# Digitizer.net
KiCad netlist of a schematic drawn in Altium Designer
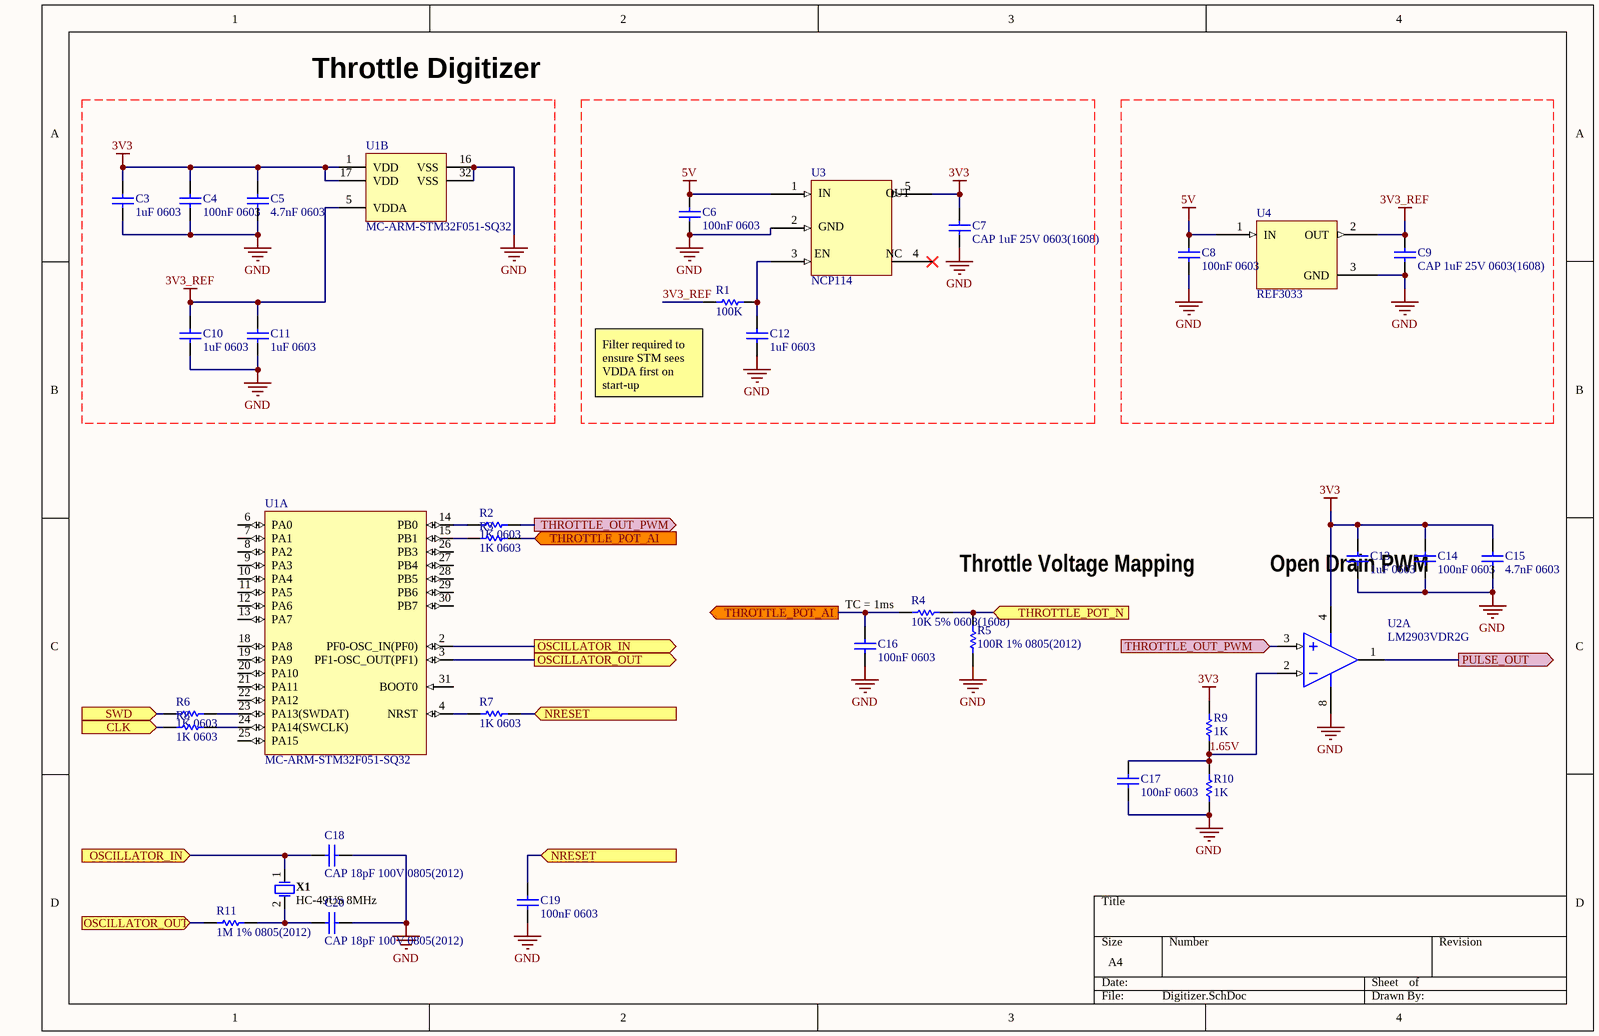
[diagram p0: Digitizer.SchDoc]

(export (version "E")
  (design (tool "Eeschema 10.0.6"))
  (components
    (comp (ref "C3")
      (value "1uF 0603")
      (footprint "CAPC0603(1608)100_M")
      (description "CAP 1uF 25V -20% to +80% 0603 (1608 Metric) Thickness 1mm SMD")
      (fields (field (name "TOLERANCE") "-20% to +80%"))
      (libsource (lib "Altium Content Vault") (part "CMP-1035-02742-1"))
    )
    (comp (ref "C4")
      (value "100nF 0603")
      (footprint "CAPC0603(1608)100_M")
      (description "CAP 1uF 25V -20% to +80% 0603 (1608 Metric) Thickness 1mm SMD")
      (fields (field (name "TOLERANCE") "-20% to +80%"))
      (libsource (lib "Altium Content Vault") (part "CMP-1035-02742-1"))
    )
    (comp (ref "C5")
      (value "4.7nF 0603")
      (footprint "CAPC0603(1608)100_M")
      (description "CAP 1uF 25V -20% to +80% 0603 (1608 Metric) Thickness 1mm SMD")
      (fields (field (name "TOLERANCE") "-20% to +80%"))
      (libsource (lib "Altium Content Vault") (part "CMP-1035-02742-1"))
    )
    (comp (ref "C6")
      (value "100nF 0603")
      (footprint "CAPC0603(1608)100_M")
      (description "CAP 1uF 25V -20% to +80% 0603 (1608 Metric) Thickness 1mm SMD")
      (fields (field (name "TOLERANCE") "-20% to +80%"))
      (libsource (lib "Altium Content Vault") (part "CMP-1035-02742-1"))
    )
    (comp (ref "C7")
      (value "CAP 1uF 25V 0603(1608)")
      (footprint "CAPC0603(1608)100_M")
      (description "CAP 1uF 25V -20% to +80% 0603 (1608 Metric) Thickness 1mm SMD")
      (fields (field (name "TOLERANCE") "-20% to +80%"))
      (libsource (lib "Altium Content Vault") (part "CAP"))
    )
    (comp (ref "C8")
      (value "100nF 0603")
      (footprint "CAPC0603(1608)100_M")
      (description "CAP 1uF 25V -20% to +80% 0603 (1608 Metric) Thickness 1mm SMD")
      (fields (field (name "TOLERANCE") "-20% to +80%"))
      (libsource (lib "Altium Content Vault") (part "CMP-1035-02742-1"))
    )
    (comp (ref "C9")
      (value "CAP 1uF 25V 0603(1608)")
      (footprint "CAPC0603(1608)100_M")
      (description "CAP 1uF 25V -20% to +80% 0603 (1608 Metric) Thickness 1mm SMD")
      (fields (field (name "TOLERANCE") "-20% to +80%"))
      (libsource (lib "Altium Content Vault") (part "CAP"))
    )
    (comp (ref "C10")
      (value "1uF 0603")
      (footprint "CAPC0603(1608)100_M")
      (description "CAP 1uF 25V -20% to +80% 0603 (1608 Metric) Thickness 1mm SMD")
      (fields (field (name "TOLERANCE") "-20% to +80%"))
      (libsource (lib "Altium Content Vault") (part "CMP-1035-02742-1"))
    )
    (comp (ref "C11")
      (value "1uF 0603")
      (footprint "CAPC0603(1608)100_M")
      (description "CAP 1uF 25V -20% to +80% 0603 (1608 Metric) Thickness 1mm SMD")
      (fields (field (name "TOLERANCE") "-20% to +80%"))
      (libsource (lib "Altium Content Vault") (part "CMP-1035-02742-1"))
    )
    (comp (ref "C12")
      (value "1uF 0603")
      (footprint "CAPC0603(1608)100_M")
      (description "CAP 1uF 25V -20% to +80% 0603 (1608 Metric) Thickness 1mm SMD")
      (fields (field (name "TOLERANCE") "-20% to +80%"))
      (libsource (lib "Altium Content Vault") (part "CMP-1035-02742-1"))
    )
    (comp (ref "C13")
      (value "1uF 0603")
      (footprint "CAPC0603(1608)100_M")
      (description "CAP 1uF 25V -20% to +80% 0603 (1608 Metric) Thickness 1mm SMD")
      (fields (field (name "TOLERANCE") "-20% to +80%"))
      (libsource (lib "Altium Content Vault") (part "CMP-1035-02742-1"))
    )
    (comp (ref "C14")
      (value "100nF 0603")
      (footprint "CAPC0603(1608)100_M")
      (description "CAP 1uF 25V -20% to +80% 0603 (1608 Metric) Thickness 1mm SMD")
      (fields (field (name "TOLERANCE") "-20% to +80%"))
      (libsource (lib "Altium Content Vault") (part "CMP-1035-02742-1"))
    )
    (comp (ref "C15")
      (value "4.7nF 0603")
      (footprint "CAPC0603(1608)100_M")
      (description "CAP 1uF 25V -20% to +80% 0603 (1608 Metric) Thickness 1mm SMD")
      (fields (field (name "TOLERANCE") "-20% to +80%"))
      (libsource (lib "Altium Content Vault") (part "CMP-1035-02742-1"))
    )
    (comp (ref "C16")
      (value "100nF 0603")
      (footprint "CAPC0603(1608)100_M")
      (description "CAP 1uF 25V -20% to +80% 0603 (1608 Metric) Thickness 1mm SMD")
      (fields (field (name "TOLERANCE") "-20% to +80%"))
      (libsource (lib "Altium Content Vault") (part "CMP-1035-02742-1"))
    )
    (comp (ref "C17")
      (value "100nF 0603")
      (footprint "CAPC0603(1608)100_M")
      (description "CAP 1uF 25V -20% to +80% 0603 (1608 Metric) Thickness 1mm SMD")
      (fields (field (name "TOLERANCE") "-20% to +80%"))
      (libsource (lib "Altium Content Vault") (part "CMP-1035-02742-1"))
    )
    (comp (ref "C18")
      (value "CAP 18pF 100V 0805(2012)")
      (footprint "CAPC0805(2012)145_L")
      (description "CAP 18pF 100V ±10% 0805 (2012 Metric) Thickness 1.45mm SMD")
      (fields (field (name "TOLERANCE") "Â±10%"))
      (libsource (lib "Altium Content Vault") (part "CMP-1036-01160-1"))
    )
    (comp (ref "C19")
      (value "100nF 0603")
      (footprint "CAPC0603(1608)100_M")
      (description "CAP 1uF 25V -20% to +80% 0603 (1608 Metric) Thickness 1mm SMD")
      (fields (field (name "TOLERANCE") "-20% to +80%"))
      (libsource (lib "Altium Content Vault") (part "CMP-1035-02742-1"))
    )
    (comp (ref "C20")
      (value "CAP 18pF 100V 0805(2012)")
      (footprint "CAPC0805(2012)145_L")
      (description "CAP 18pF 100V ±10% 0805 (2012 Metric) Thickness 1.45mm SMD")
      (fields (field (name "TOLERANCE") "Â±10%"))
      (libsource (lib "Altium Content Vault") (part "CMP-1036-01160-1"))
    )
    (comp (ref "R1")
      (value "100K")
      (footprint "RESC0603(1608)_N")
      (description "2K 0.1W 1% 0603 (1608 Metric)  SMD")
      (fields (field (name "POWER") "0.1 W") (field (name "TOLERANCE") "1 %"))
      (libsource (lib "Altium Content Vault") (part "CMP-1012-00542-1"))
    )
    (comp (ref "R2")
      (value "1K 0603")
      (footprint "RESC0603(1608)_N")
      (description "2K 0.1W 1% 0603 (1608 Metric)  SMD")
      (fields (field (name "POWER") "0.1 W") (field (name "TOLERANCE") "1 %"))
      (libsource (lib "Altium Content Vault") (part "CMP-1012-00542-1"))
    )
    (comp (ref "R3")
      (value "1K 0603")
      (footprint "RESC0603(1608)_N")
      (description "2K 0.1W 1% 0603 (1608 Metric)  SMD")
      (fields (field (name "POWER") "0.1 W") (field (name "TOLERANCE") "1 %"))
      (libsource (lib "Altium Content Vault") (part "CMP-1012-00542-1"))
    )
    (comp (ref "R4")
      (value "10K 5% 0603(1608)")
      (footprint "RESC0603(1608)_M")
      (description "10K 0.1W 5% 0603 (1608 Metric)  SMD")
      (fields (field (name "TOLERANCE") "5 %") (field (name "POWER") "0.1 W"))
      (libsource (lib "Altium Content Vault") (part "CMP-1012-00098-1"))
    )
    (comp (ref "R5")
      (value "100R 1% 0805(2012)")
      (footprint "RESC0805(2012)_M")
      (description "100R 0.125W 1% 0805 (2012 Metric)  SMD")
      (fields (field (name "POWER") "0.125 W") (field (name "TOLERANCE") "1 %"))
      (libsource (lib "Altium Content Vault") (part "RES"))
    )
    (comp (ref "R6")
      (value "1K 0603")
      (footprint "RESC0603(1608)_N")
      (description "2K 0.1W 1% 0603 (1608 Metric)  SMD")
      (fields (field (name "POWER") "0.1 W") (field (name "TOLERANCE") "1 %"))
      (libsource (lib "Altium Content Vault") (part "CMP-1012-00542-1"))
    )
    (comp (ref "R7")
      (value "1K 0603")
      (footprint "RESC0603(1608)_N")
      (description "2K 0.1W 1% 0603 (1608 Metric)  SMD")
      (fields (field (name "POWER") "0.1 W") (field (name "TOLERANCE") "1 %"))
      (libsource (lib "Altium Content Vault") (part "CMP-1012-00542-1"))
    )
    (comp (ref "R8")
      (value "1K 0603")
      (footprint "RESC0603(1608)_N")
      (description "2K 0.1W 1% 0603 (1608 Metric)  SMD")
      (fields (field (name "POWER") "0.1 W") (field (name "TOLERANCE") "1 %"))
      (libsource (lib "Altium Content Vault") (part "CMP-1012-00542-1"))
    )
    (comp (ref "R9")
      (value "1K")
      (footprint "RESC0603(1608)_N")
      (description "2K 0.1W 1% 0603 (1608 Metric)  SMD")
      (fields (field (name "POWER") "0.1 W") (field (name "TOLERANCE") "1 %"))
      (libsource (lib "Altium Content Vault") (part "CMP-1012-00542-1"))
    )
    (comp (ref "R10")
      (value "1K")
      (footprint "RESC0603(1608)_N")
      (description "2K 0.1W 1% 0603 (1608 Metric)  SMD")
      (fields (field (name "POWER") "0.1 W") (field (name "TOLERANCE") "1 %"))
      (libsource (lib "Altium Content Vault") (part "CMP-1012-00542-1"))
    )
    (comp (ref "R11")
      (value "1M 1% 0805(2012)")
      (footprint "RESC0805(2012)_M")
      (description "1M 0.125W 1% 0805 (2012 Metric)  SMD")
      (fields (field (name "POWER") "0.125 W") (field (name "TOLERANCE") "1 %"))
      (libsource (lib "Altium Content Vault") (part "RES"))
    )
    (comp (ref "U1")
      (value "MC-ARM-STM32F051-SQ32")
      (footprint "STM-LQFP32_N")
      (libsource (lib "EV_library") (part "MC-ARM-STM32F051-SQ32"))
    )
    (comp (ref "U2")
      (value "LM2903VDR2G")
      (footprint "ONSC-SOIC-8-751-07_V")
      (fields (field (name "MANUFACTURER") "On Semiconductor"))
      (libsource (lib "Altium Content Vault") (part "ONSC-LM2903X_X93_LMV393_NVC2903-8"))
    )
    (comp (ref "U3") (value "NCP114") (footprint "SOT23-5_N") (libsource (lib "EV_library") (part "NCP114")))
    (comp (ref "U4") (value "REF3033") (footprint "SOT23-3") (libsource (lib "EV_library") (part "REF3033")))
    (comp (ref "X1")
      (value "HC-49US 8MHz")
      (footprint "JPY-HC-49US")
      (description "Crystal, 16 MHz, +/- 30 ppm, 18 pF, -20 to 70 degC, 2-Pin THD")
      (fields (field (name "MANUFACTURER") "Jing peng yuan"))
      (libsource (lib "Altium Content Vault") (part "XTAL-1-2-2"))
    )
  )
  (nets
    (net (code "1") (name "/1.65V") (class "Default")
      (node (ref "C17") (pin "2") (pinfunction "2_2") (pintype "passive"))
      (node (ref "R10") (pin "2") (pinfunction "2_2") (pintype "passive"))
      (node (ref "R9") (pin "1") (pinfunction "1_1") (pintype "passive"))
      (node (ref "U2") (pin "2") (pinfunction "INA-_2") (pintype "input"))
    )
    (net (code "2") (name "/CLK") (class "Default")
      (node (ref "R8") (pin "1") (pinfunction "1_1") (pintype "passive"))
    )
    (net (code "3") (name "/NRESET") (class "Default")
      (node (ref "C19") (pin "2") (pinfunction "2_2") (pintype "passive"))
      (node (ref "R7") (pin "2") (pinfunction "2_2") (pintype "passive"))
    )
    (net (code "4") (name "/OSCILLATOR_IN") (class "Default")
      (node (ref "C18") (pin "1") (pinfunction "1_1") (pintype "passive"))
      (node (ref "U1") (pin "2") (pinfunction "PF0-OSC_IN(PF0)_2") (pintype "bidirectional"))
      (node (ref "X1") (pin "1") (pinfunction "1_1") (pintype "passive"))
    )
    (net (code "5") (name "/OSCILLATOR_OUT") (class "Default")
      (node (ref "R11") (pin "1") (pinfunction "1_1") (pintype "passive"))
      (node (ref "U1") (pin "3") (pinfunction "PF1-OSC_OUT(PF1)_3") (pintype "bidirectional"))
    )
    (net (code "6") (name "/PULSE_OUT") (class "Default")
      (node (ref "U2") (pin "1") (pinfunction "OUTA_1") (pintype "open_collector"))
    )
    (net (code "7") (name "/SWD") (class "Default")
      (node (ref "R6") (pin "1") (pinfunction "1_1") (pintype "passive"))
    )
    (net (code "8") (name "/THROTTLE_OUT_PWM") (class "Default")
      (node (ref "R2") (pin "2") (pinfunction "2_2") (pintype "passive"))
      (node (ref "U2") (pin "3") (pinfunction "INA+_3") (pintype "input"))
    )
    (net (code "9") (name "/THROTTLE_POT_AI") (class "Default")
      (node (ref "C16") (pin "2") (pinfunction "2_2") (pintype "passive"))
      (node (ref "R3") (pin "2") (pinfunction "2_2") (pintype "passive"))
      (node (ref "R4") (pin "1") (pinfunction "1_1") (pintype "passive"))
    )
    (net (code "10") (name "/THROTTLE_POT_N") (class "Default")
      (node (ref "R4") (pin "2") (pinfunction "2_2") (pintype "passive"))
      (node (ref "R5") (pin "2") (pinfunction "2_2") (pintype "passive"))
    )
    (net (code "11") (name "3V3") (class "Default")
      (node (ref "C13") (pin "2") (pinfunction "2_2") (pintype "passive"))
      (node (ref "C14") (pin "2") (pinfunction "2_2") (pintype "passive"))
      (node (ref "C15") (pin "2") (pinfunction "2_2") (pintype "passive"))
      (node (ref "C3") (pin "2") (pinfunction "2_2") (pintype "passive"))
      (node (ref "C4") (pin "2") (pinfunction "2_2") (pintype "passive"))
      (node (ref "C5") (pin "2") (pinfunction "2_2") (pintype "passive"))
      (node (ref "C7") (pin "2") (pinfunction "2_2") (pintype "passive"))
      (node (ref "R9") (pin "2") (pinfunction "2_2") (pintype "passive"))
      (node (ref "U1") (pin "1") (pinfunction "VDD_1") (pintype "power_in"))
      (node (ref "U1") (pin "17") (pinfunction "VDD_17") (pintype "power_in"))
      (node (ref "U2") (pin "4") (pinfunction "GND_4") (pintype "power_in"))
      (node (ref "U3") (pin "5") (pinfunction "OUT_5") (pintype "output"))
    )
    (net (code "12") (name "3V3_REF") (class "Default")
      (node (ref "C10") (pin "2") (pinfunction "2_2") (pintype "passive"))
      (node (ref "C11") (pin "2") (pinfunction "2_2") (pintype "passive"))
      (node (ref "C9") (pin "2") (pinfunction "2_2") (pintype "passive"))
      (node (ref "R1") (pin "1") (pinfunction "1_1") (pintype "passive"))
      (node (ref "U1") (pin "5") (pinfunction "VDDA_5") (pintype "power_in"))
      (node (ref "U4") (pin "2") (pinfunction "OUT_2") (pintype "output"))
    )
    (net (code "13") (name "5V") (class "Default")
      (node (ref "C6") (pin "2") (pinfunction "2_2") (pintype "passive"))
      (node (ref "C8") (pin "2") (pinfunction "2_2") (pintype "passive"))
      (node (ref "U3") (pin "1") (pinfunction "IN_1") (pintype "input"))
      (node (ref "U4") (pin "1") (pinfunction "IN_1") (pintype "input"))
    )
    (net (code "14") (name "GND") (class "Default")
      (node (ref "C10") (pin "1") (pinfunction "1_1") (pintype "passive"))
      (node (ref "C11") (pin "1") (pinfunction "1_1") (pintype "passive"))
      (node (ref "C12") (pin "1") (pinfunction "1_1") (pintype "passive"))
      (node (ref "C13") (pin "1") (pinfunction "1_1") (pintype "passive"))
      (node (ref "C14") (pin "1") (pinfunction "1_1") (pintype "passive"))
      (node (ref "C15") (pin "1") (pinfunction "1_1") (pintype "passive"))
      (node (ref "C16") (pin "1") (pinfunction "1_1") (pintype "passive"))
      (node (ref "C17") (pin "1") (pinfunction "1_1") (pintype "passive"))
      (node (ref "C18") (pin "2") (pinfunction "2_2") (pintype "passive"))
      (node (ref "C19") (pin "1") (pinfunction "1_1") (pintype "passive"))
      (node (ref "C20") (pin "2") (pinfunction "2_2") (pintype "passive"))
      (node (ref "C3") (pin "1") (pinfunction "1_1") (pintype "passive"))
      (node (ref "C4") (pin "1") (pinfunction "1_1") (pintype "passive"))
      (node (ref "C5") (pin "1") (pinfunction "1_1") (pintype "passive"))
      (node (ref "C6") (pin "1") (pinfunction "1_1") (pintype "passive"))
      (node (ref "C7") (pin "1") (pinfunction "1_1") (pintype "passive"))
      (node (ref "C8") (pin "1") (pinfunction "1_1") (pintype "passive"))
      (node (ref "C9") (pin "1") (pinfunction "1_1") (pintype "passive"))
      (node (ref "R10") (pin "1") (pinfunction "1_1") (pintype "passive"))
      (node (ref "R5") (pin "1") (pinfunction "1_1") (pintype "passive"))
      (node (ref "U1") (pin "16") (pinfunction "VSS_16") (pintype "power_in"))
      (node (ref "U1") (pin "32") (pinfunction "VSS_32") (pintype "power_in"))
      (node (ref "U2") (pin "8") (pinfunction "VCC_8") (pintype "power_in"))
      (node (ref "U3") (pin "2") (pinfunction "GND_2") (pintype "input"))
      (node (ref "U4") (pin "3") (pinfunction "GND_3") (pintype "passive"))
    )
    (net (code "15") (name "Net-(C20-Pad1)") (class "Default")
      (node (ref "C20") (pin "1") (pinfunction "1_1") (pintype "passive"))
      (node (ref "R11") (pin "2") (pinfunction "2_2") (pintype "passive"))
      (node (ref "X1") (pin "2") (pinfunction "2_2") (pintype "passive"))
    )
    (net (code "16") (name "Net-(U1A-NRST)") (class "Default")
      (node (ref "R7") (pin "1") (pinfunction "1_1") (pintype "passive"))
      (node (ref "U1") (pin "4") (pinfunction "NRST_4") (pintype "bidirectional"))
    )
    (net (code "17") (name "Net-(U1A-PA13(SWDAT))") (class "Default")
      (node (ref "R6") (pin "2") (pinfunction "2_2") (pintype "passive"))
      (node (ref "U1") (pin "23") (pinfunction "PA13(SWDAT)_23") (pintype "bidirectional"))
    )
    (net (code "18") (name "Net-(U1A-PA14(SWCLK))") (class "Default")
      (node (ref "R8") (pin "2") (pinfunction "2_2") (pintype "passive"))
      (node (ref "U1") (pin "24") (pinfunction "PA14(SWCLK)_24") (pintype "bidirectional"))
    )
    (net (code "19") (name "Net-(U1A-PB0)") (class "Default")
      (node (ref "R2") (pin "1") (pinfunction "1_1") (pintype "passive"))
      (node (ref "U1") (pin "14") (pinfunction "PB0_14") (pintype "bidirectional"))
    )
    (net (code "20") (name "Net-(U1A-PB1)") (class "Default")
      (node (ref "R3") (pin "1") (pinfunction "1_1") (pintype "passive"))
      (node (ref "U1") (pin "15") (pinfunction "PB1_15") (pintype "bidirectional"))
    )
    (net (code "21") (name "Net-(U3-EN)") (class "Default")
      (node (ref "C12") (pin "2") (pinfunction "2_2") (pintype "passive"))
      (node (ref "R1") (pin "2") (pinfunction "2_2") (pintype "passive"))
      (node (ref "U3") (pin "3") (pinfunction "EN_3") (pintype "input"))
    )
    (net (code "22") (name "unconnected-(U1A-BOOT0-Pad31)") (class "Default")
      (node (ref "U1") (pin "31") (pinfunction "BOOT0_31") (pintype "input"))
    )
    (net (code "23") (name "unconnected-(U1A-PA0-Pad6)") (class "Default")
      (node (ref "U1") (pin "6") (pinfunction "PA0_6") (pintype "bidirectional"))
    )
    (net (code "24") (name "unconnected-(U1A-PA1-Pad7)") (class "Default")
      (node (ref "U1") (pin "7") (pinfunction "PA1_7") (pintype "bidirectional"))
    )
    (net (code "25") (name "unconnected-(U1A-PA2-Pad8)") (class "Default")
      (node (ref "U1") (pin "8") (pinfunction "PA2_8") (pintype "bidirectional"))
    )
    (net (code "26") (name "unconnected-(U1A-PA3-Pad9)") (class "Default")
      (node (ref "U1") (pin "9") (pinfunction "PA3_9") (pintype "bidirectional"))
    )
    (net (code "27") (name "unconnected-(U1A-PA4-Pad10)") (class "Default")
      (node (ref "U1") (pin "10") (pinfunction "PA4_10") (pintype "bidirectional"))
    )
    (net (code "28") (name "unconnected-(U1A-PA5-Pad11)") (class "Default")
      (node (ref "U1") (pin "11") (pinfunction "PA5_11") (pintype "bidirectional"))
    )
    (net (code "29") (name "unconnected-(U1A-PA6-Pad12)") (class "Default")
      (node (ref "U1") (pin "12") (pinfunction "PA6_12") (pintype "bidirectional"))
    )
    (net (code "30") (name "unconnected-(U1A-PA7-Pad13)") (class "Default")
      (node (ref "U1") (pin "13") (pinfunction "PA7_13") (pintype "bidirectional"))
    )
    (net (code "31") (name "unconnected-(U1A-PA8-Pad18)") (class "Default")
      (node (ref "U1") (pin "18") (pinfunction "PA8_18") (pintype "bidirectional"))
    )
    (net (code "32") (name "unconnected-(U1A-PA9-Pad19)") (class "Default")
      (node (ref "U1") (pin "19") (pinfunction "PA9_19") (pintype "bidirectional"))
    )
    (net (code "33") (name "unconnected-(U1A-PA10-Pad20)") (class "Default")
      (node (ref "U1") (pin "20") (pinfunction "PA10_20") (pintype "bidirectional"))
    )
    (net (code "34") (name "unconnected-(U1A-PA11-Pad21)") (class "Default")
      (node (ref "U1") (pin "21") (pinfunction "PA11_21") (pintype "bidirectional"))
    )
    (net (code "35") (name "unconnected-(U1A-PA12-Pad22)") (class "Default")
      (node (ref "U1") (pin "22") (pinfunction "PA12_22") (pintype "bidirectional"))
    )
    (net (code "36") (name "unconnected-(U1A-PA15-Pad25)") (class "Default")
      (node (ref "U1") (pin "25") (pinfunction "PA15_25") (pintype "bidirectional"))
    )
    (net (code "37") (name "unconnected-(U1A-PB3-Pad26)") (class "Default")
      (node (ref "U1") (pin "26") (pinfunction "PB3_26") (pintype "bidirectional"))
    )
    (net (code "38") (name "unconnected-(U1A-PB4-Pad27)") (class "Default")
      (node (ref "U1") (pin "27") (pinfunction "PB4_27") (pintype "bidirectional"))
    )
    (net (code "39") (name "unconnected-(U1A-PB5-Pad28)") (class "Default")
      (node (ref "U1") (pin "28") (pinfunction "PB5_28") (pintype "bidirectional"))
    )
    (net (code "40") (name "unconnected-(U1A-PB6-Pad29)") (class "Default")
      (node (ref "U1") (pin "29") (pinfunction "PB6_29") (pintype "bidirectional"))
    )
    (net (code "41") (name "unconnected-(U1A-PB7-Pad30)") (class "Default")
      (node (ref "U1") (pin "30") (pinfunction "PB7_30") (pintype "bidirectional"))
    )
    (net (code "42") (name "unconnected-(U3-NC-Pad4)") (class "Default")
      (node (ref "U3") (pin "4") (pinfunction "NC_4") (pintype "passive"))
    )
  )
)
